# CP2102N_USB-to-UART_Bridge.net
KiCad netlist of a schematic drawn in Altium Designer
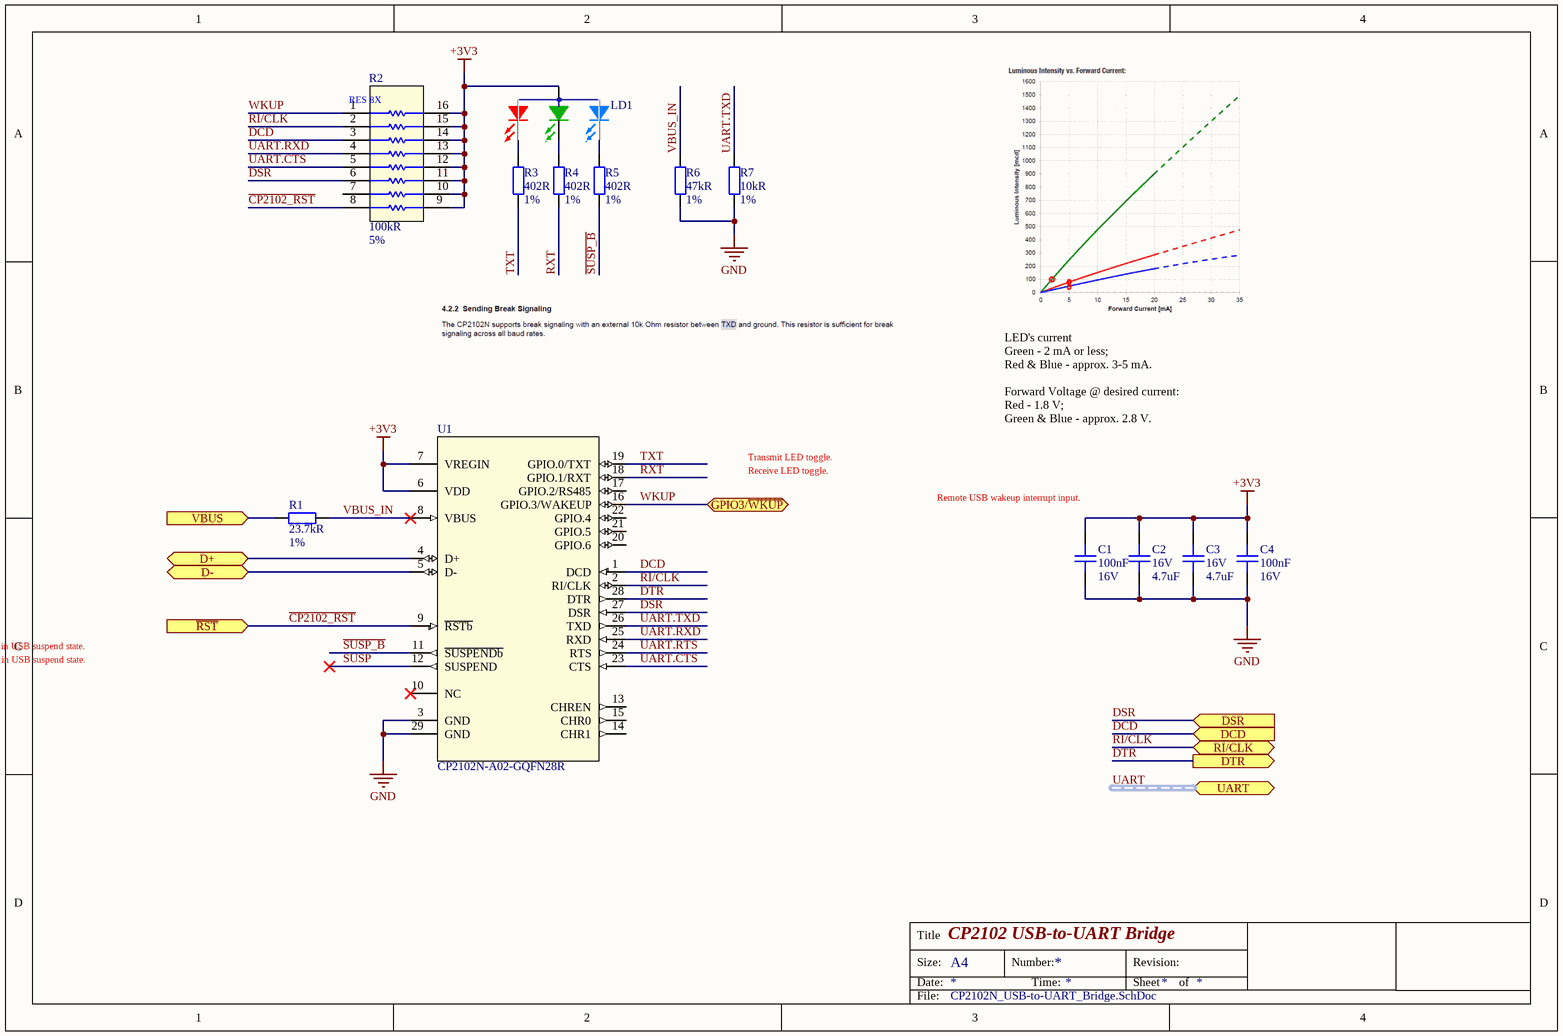
[diagram p0: CP2102N_USB-to-UART_Bridge.SchDoc]

(export (version "E")
  (design (tool "Eeschema 10.0.6"))
  (components
    (comp (ref "C1")
      (value "CAP CER 0.1UF 16V X7R 0402")
      (footprint "C0402")
      (description "0.1µF ±10% 16V Ceramic Capacitor X7R 0402 (1005 Metric)")
      (fields
        (field (name "MANUFACTURER PART NUMBER") "CC0402KRX7R7BB104")
        (field (name "MANUFACTURER") "Yageo")
        (field (name "CAPACITANCE") "100nF")
        (field (name "VOLTAGE") "16V")
      )
      (libsource (lib "capacitors_smd") (part "CAP CER 0.1UF 16V X7R 0402"))
    )
    (comp (ref "C2")
      (value "CAP CER 4.7UF 16V X5R 0603")
      (footprint "C0603")
      (description "4.7µF ±10% 16V Ceramic Capacitor X5R 0603 (1608 Metric)")
      (fields
        (field (name "MANUFACTURER") "Yageo")
        (field (name "MANUFACTURER PART NUMBER") "CC0603KRX5R7BB475")
        (field (name "VOLTAGE RATING") "16V")
        (field (name "CAPACITANCE") "4.7uF")
      )
      (libsource (lib "capacitors_smd") (part "CAP CER 4.7UF 16V X5R 0603"))
    )
    (comp (ref "C3")
      (value "CAP CER 4.7UF 16V X5R 0603")
      (footprint "C0603")
      (description "4.7µF ±10% 16V Ceramic Capacitor X5R 0603 (1608 Metric)")
      (fields
        (field (name "MANUFACTURER") "Yageo")
        (field (name "MANUFACTURER PART NUMBER") "CC0603KRX5R7BB475")
        (field (name "VOLTAGE RATING") "16V")
        (field (name "CAPACITANCE") "4.7uF")
      )
      (libsource (lib "capacitors_smd") (part "CAP CER 4.7UF 16V X5R 0603"))
    )
    (comp (ref "C4")
      (value "CAP CER 0.1UF 16V X7R 0402")
      (footprint "C0402")
      (description "0.1µF ±10% 16V Ceramic Capacitor X7R 0402 (1005 Metric)")
      (fields
        (field (name "MANUFACTURER PART NUMBER") "CC0402KRX7R7BB104")
        (field (name "MANUFACTURER") "Yageo")
        (field (name "CAPACITANCE") "100nF")
        (field (name "VOLTAGE") "16V")
      )
      (libsource (lib "capacitors_smd") (part "CAP CER 0.1UF 16V X7R 0402"))
    )
    (comp (ref "LD1")
      (value "150066M153000")
      (footprint "LED_0606_RGB_WURTH")
      (fields (field (name "MANUFACTURER") "Wurth Electronics"))
      (libsource (lib "BLDC_Motor_Driver") (part "LED RGB DIFFUSED SMD"))
    )
    (comp (ref "R1")
      (value "RES SMD 23.7K OHM 1% 1/16W 0402")
      (footprint "R0402")
      (description "23.7 kOhms ±1% 0.063W, 1/16W Chip Resistor 0402 (1005 Metric) Moisture Resistant Thick Film")
      (fields
        (field (name "MANUFACTURER") "Yageo")
        (field (name "MANUFACTURER PART NUMBER") "RC0402FR-0723K7L")
        (field (name "RESISTANCE") "23.7kR")
        (field (name "TOLERANCE") "1%")
      )
      (libsource (lib "resistors_smd") (part "RES SMD 23.7K OHM 1% 1/16W 0402"))
    )
    (comp (ref "R2")
      (value "RES ARRAY 8 RES 100K OHM 1606")
      (footprint "YAG_YC248")
      (fields
        (field (name "MANUFACTURER") "Yageo")
        (field (name "MANUFACTURER PART NUMBER") "YC248-JR-07100KL")
        (field (name "RESISTANCE") "100kR")
        (field (name "TOLERANCE") "5%")
      )
      (libsource (lib "resistors_smd") (part "RES ARRAY 8 RES 100K OHM 1606"))
    )
    (comp (ref "R3")
      (value "RES SMD 402 OHM 1% 1/16W 0402")
      (footprint "R0402")
      (description "402 Ohms ±1% 0.063W, 1/16W Chip Resistor 0402 (1005 Metric) Moisture Resistant Thick Film")
      (fields
        (field (name "MANUFACTURER") "Yageo")
        (field (name "MANUFACTURER PART NUMBER") "RC0402FR-07402RL")
        (field (name "RESISTANCE") "402R")
        (field (name "TOLERANCE") "1%")
      )
      (libsource (lib "resistors_smd") (part "RES SMD 402 OHM 1% 1/16W 0402"))
    )
    (comp (ref "R4")
      (value "RES SMD 402 OHM 1% 1/16W 0402")
      (footprint "R0402")
      (description "402 Ohms ±1% 0.063W, 1/16W Chip Resistor 0402 (1005 Metric) Moisture Resistant Thick Film")
      (fields
        (field (name "MANUFACTURER") "Yageo")
        (field (name "MANUFACTURER PART NUMBER") "RC0402FR-07402RL")
        (field (name "RESISTANCE") "402R")
        (field (name "TOLERANCE") "1%")
      )
      (libsource (lib "resistors_smd") (part "RES SMD 402 OHM 1% 1/16W 0402"))
    )
    (comp (ref "R5")
      (value "RES SMD 402 OHM 1% 1/16W 0402")
      (footprint "R0402")
      (description "402 Ohms ±1% 0.063W, 1/16W Chip Resistor 0402 (1005 Metric) Moisture Resistant Thick Film")
      (fields
        (field (name "MANUFACTURER") "Yageo")
        (field (name "MANUFACTURER PART NUMBER") "RC0402FR-07402RL")
        (field (name "RESISTANCE") "402R")
        (field (name "TOLERANCE") "1%")
      )
      (libsource (lib "resistors_smd") (part "RES SMD 402 OHM 1% 1/16W 0402"))
    )
    (comp (ref "R6")
      (value "RES SMD 47K OHM 1% 1/16W 0402")
      (footprint "R0402")
      (description "47 kOhms ±1% 0.063W, 1/16W Chip Resistor 0402 (1005 Metric) Moisture Resistant Thick Film")
      (fields
        (field (name "MANUFACTURER PART NUMBER") "RC0402FR-0747KL")
        (field (name "MANUFACTURER") "Yageo")
        (field (name "RESISTANCE") "47kR")
        (field (name "TOLERANCE") "1%")
      )
      (libsource (lib "resistors_smd") (part "RES SMD 47K OHM 1% 1/16W 0402"))
    )
    (comp (ref "R7")
      (value "RES SMD 10K OHM 1% 1/16W 0402")
      (footprint "R0402")
      (description "10 kOhms ±1% 0.063W, 1/16W Chip Resistor 0402 (1005 Metric) Moisture Resistant Thick Film")
      (fields
        (field (name "MANUFACTURER PART NUMBER") "RC0402FR-0710KP")
        (field (name "MANUFACTURER") "Yageo")
        (field (name "RESISTANCE") "10kR")
        (field (name "TOLERANCE") "1%")
      )
      (libsource (lib "resistors_smd") (part "RES SMD 10K OHM 1% 1/16W 0402"))
    )
    (comp (ref "U1")
      (value "CP2102N-A02-GQFN28R")
      (footprint "QFN28_5X5")
      (description "USB Bridge, USB to UART USB 2.0 UART Interface 28-QFN (5x5)")
      (fields (field (name "MANUFACTURER") "Silicon Labs"))
      (libsource (lib "BLDC_Moto_Driver") (part "IC CP2102N USB TO UART BRIDGE QFN28"))
    )
  )
  (nets
    (net (code "2") (name "+3V3") (class "Default")
      (node (ref "C1") (pin "2") (pinfunction "2_2") (pintype "passive"))
      (node (ref "C2") (pin "2") (pinfunction "2_2") (pintype "passive"))
      (node (ref "C3") (pin "2") (pinfunction "2_2") (pintype "passive"))
      (node (ref "C4") (pin "2") (pinfunction "2_2") (pintype "passive"))
      (node (ref "LD1") (pin "A") (pinfunction "A_A") (pintype "passive"))
      (node (ref "R2") (pin "10") (pinfunction "110_10") (pintype "passive"))
      (node (ref "R2") (pin "11") (pinfunction "111_11") (pintype "passive"))
      (node (ref "R2") (pin "12") (pinfunction "112_12") (pintype "passive"))
      (node (ref "R2") (pin "13") (pinfunction "113_13") (pintype "passive"))
      (node (ref "R2") (pin "14") (pinfunction "114_14") (pintype "passive"))
      (node (ref "R2") (pin "15") (pinfunction "115_15") (pintype "passive"))
      (node (ref "R2") (pin "16") (pinfunction "116_16") (pintype "passive"))
      (node (ref "R2") (pin "9") (pinfunction "19_9") (pintype "passive"))
      (node (ref "U1") (pin "6") (pinfunction "VDD_6") (pintype "power_in"))
      (node (ref "U1") (pin "7") (pinfunction "VREGIN_7") (pintype "power_in"))
    )
    (net (code "3") (name "/CP2102_RST") (class "Default")
      (node (ref "R2") (pin "8") (pinfunction "18_8") (pintype "passive"))
      (node (ref "U1") (pin "9") (pinfunction "RSTb_9") (pintype "input"))
    )
    (net (code "4") (name "/D+") (class "Default")
      (node (ref "U1") (pin "4") (pinfunction "D+_4") (pintype "bidirectional"))
    )
    (net (code "5") (name "/D-") (class "Default")
      (node (ref "U1") (pin "5") (pinfunction "D-_5") (pintype "bidirectional"))
    )
    (net (code "6") (name "/DCD") (class "Default")
      (node (ref "R2") (pin "3") (pinfunction "13_3") (pintype "passive"))
      (node (ref "U1") (pin "1") (pinfunction "DCD_1") (pintype "input"))
    )
    (net (code "7") (name "/DSR") (class "Default")
      (node (ref "R2") (pin "6") (pinfunction "16_6") (pintype "passive"))
      (node (ref "U1") (pin "27") (pinfunction "DSR_27") (pintype "input"))
    )
    (net (code "8") (name "/DTR") (class "Default")
      (node (ref "U1") (pin "28") (pinfunction "DTR_28") (pintype "output"))
    )
    (net (code "9") (name "/RI{slash}CLK") (class "Default")
      (node (ref "R2") (pin "2") (pinfunction "12_2") (pintype "passive"))
      (node (ref "U1") (pin "2") (pinfunction "RI/CLK_2") (pintype "bidirectional"))
    )
    (net (code "10") (name "/RXT") (class "Default")
      (node (ref "R4") (pin "1") (pinfunction "1_1") (pintype "passive"))
      (node (ref "U1") (pin "18") (pinfunction "GPIO.1/RXT_18") (pintype "bidirectional"))
    )
    (net (code "11") (name "/SUSP") (class "Default")
      (node (ref "U1") (pin "12") (pinfunction "SUSPEND_12") (pintype "output+no_connect"))
    )
    (net (code "12") (name "/SUSP_B") (class "Default")
      (node (ref "R5") (pin "1") (pinfunction "1_1") (pintype "passive"))
      (node (ref "U1") (pin "11") (pinfunction "SUSPENDb_11") (pintype "output"))
    )
    (net (code "13") (name "/TXT") (class "Default")
      (node (ref "R3") (pin "1") (pinfunction "1_1") (pintype "passive"))
      (node (ref "U1") (pin "19") (pinfunction "GPIO.0/TXT_19") (pintype "bidirectional"))
    )
    (net (code "14") (name "/UART.CTS") (class "Default")
      (node (ref "R2") (pin "5") (pinfunction "15_5") (pintype "passive"))
      (node (ref "U1") (pin "23") (pinfunction "CTS_23") (pintype "input"))
    )
    (net (code "15") (name "/UART.RTS") (class "Default")
      (node (ref "U1") (pin "24") (pinfunction "RTS_24") (pintype "output"))
    )
    (net (code "16") (name "/UART.RXD") (class "Default")
      (node (ref "R2") (pin "4") (pinfunction "14_4") (pintype "passive"))
      (node (ref "U1") (pin "25") (pinfunction "RXD_25") (pintype "input"))
    )
    (net (code "17") (name "/UART.TXD") (class "Default")
      (node (ref "R7") (pin "2") (pinfunction "2_2") (pintype "passive"))
      (node (ref "U1") (pin "26") (pinfunction "TXD_26") (pintype "output"))
    )
    (net (code "18") (name "/VBUS") (class "Default")
      (node (ref "R1") (pin "2") (pinfunction "2_2") (pintype "passive"))
    )
    (net (code "19") (name "/VBUS_IN") (class "Default")
      (node (ref "R1") (pin "1") (pinfunction "1_1") (pintype "passive"))
      (node (ref "R6") (pin "1") (pinfunction "1_1") (pintype "passive"))
      (node (ref "U1") (pin "8") (pinfunction "VBUS_8") (pintype "input"))
    )
    (net (code "20") (name "/WKUP") (class "Default")
      (node (ref "R2") (pin "1") (pinfunction "11_1") (pintype "passive"))
      (node (ref "U1") (pin "16") (pinfunction "GPIO.3/WAKEUP_16") (pintype "bidirectional"))
    )
    (net (code "22") (name "GND") (class "Default")
      (node (ref "C1") (pin "1") (pinfunction "1_1") (pintype "passive"))
      (node (ref "C2") (pin "1") (pinfunction "1_1") (pintype "passive"))
      (node (ref "C3") (pin "1") (pinfunction "1_1") (pintype "passive"))
      (node (ref "C4") (pin "1") (pinfunction "1_1") (pintype "passive"))
      (node (ref "R6") (pin "2") (pinfunction "2_2") (pintype "passive"))
      (node (ref "R7") (pin "1") (pinfunction "1_1") (pintype "passive"))
      (node (ref "U1") (pin "29") (pinfunction "GND_29") (pintype "power_in"))
      (node (ref "U1") (pin "3") (pinfunction "GND_3") (pintype "power_in"))
    )
    (net (code "23") (name "Net-(LD1-PadBK)") (class "Default")
      (node (ref "LD1") (pin "BK") (pinfunction "BK_BK") (pintype "passive"))
      (node (ref "R5") (pin "2") (pinfunction "2_2") (pintype "passive"))
    )
    (net (code "24") (name "Net-(LD1-PadGK)") (class "Default")
      (node (ref "LD1") (pin "GK") (pinfunction "GK_GK") (pintype "passive"))
      (node (ref "R4") (pin "2") (pinfunction "2_2") (pintype "passive"))
    )
    (net (code "25") (name "Net-(LD1-PadRK)") (class "Default")
      (node (ref "LD1") (pin "RK") (pinfunction "RK_RK") (pintype "passive"))
      (node (ref "R3") (pin "2") (pinfunction "2_2") (pintype "passive"))
    )
    (net (code "26") (name "unconnected-(R2-17-Pad7)") (class "Default")
      (node (ref "R2") (pin "7") (pinfunction "17_7") (pintype "passive"))
    )
    (net (code "27") (name "unconnected-(U1-CHR0-Pad15)") (class "Default")
      (node (ref "U1") (pin "15") (pinfunction "CHR0_15") (pintype "output"))
    )
    (net (code "28") (name "unconnected-(U1-CHR1-Pad14)") (class "Default")
      (node (ref "U1") (pin "14") (pinfunction "CHR1_14") (pintype "output"))
    )
    (net (code "29") (name "unconnected-(U1-CHREN-Pad13)") (class "Default")
      (node (ref "U1") (pin "13") (pinfunction "CHREN_13") (pintype "output"))
    )
    (net (code "30") (name "unconnected-(U1-GPIO.2{slash}RS485-Pad17)") (class "Default")
      (node (ref "U1") (pin "17") (pinfunction "GPIO.2/RS485_17") (pintype "bidirectional"))
    )
    (net (code "31") (name "unconnected-(U1-GPIO.4-Pad22)") (class "Default")
      (node (ref "U1") (pin "22") (pinfunction "GPIO.4_22") (pintype "bidirectional"))
    )
    (net (code "32") (name "unconnected-(U1-GPIO.5-Pad21)") (class "Default")
      (node (ref "U1") (pin "21") (pinfunction "GPIO.5_21") (pintype "bidirectional"))
    )
    (net (code "33") (name "unconnected-(U1-GPIO.6-Pad20)") (class "Default")
      (node (ref "U1") (pin "20") (pinfunction "GPIO.6_20") (pintype "bidirectional"))
    )
    (net (code "34") (name "unconnected-(U1-NC-Pad10)") (class "Default")
      (node (ref "U1") (pin "10") (pinfunction "NC_10") (pintype "passive+no_connect"))
    )
  )
)
